# SMU_STPM_Board.net
KiCad netlist of a schematic drawn in Altium Designer
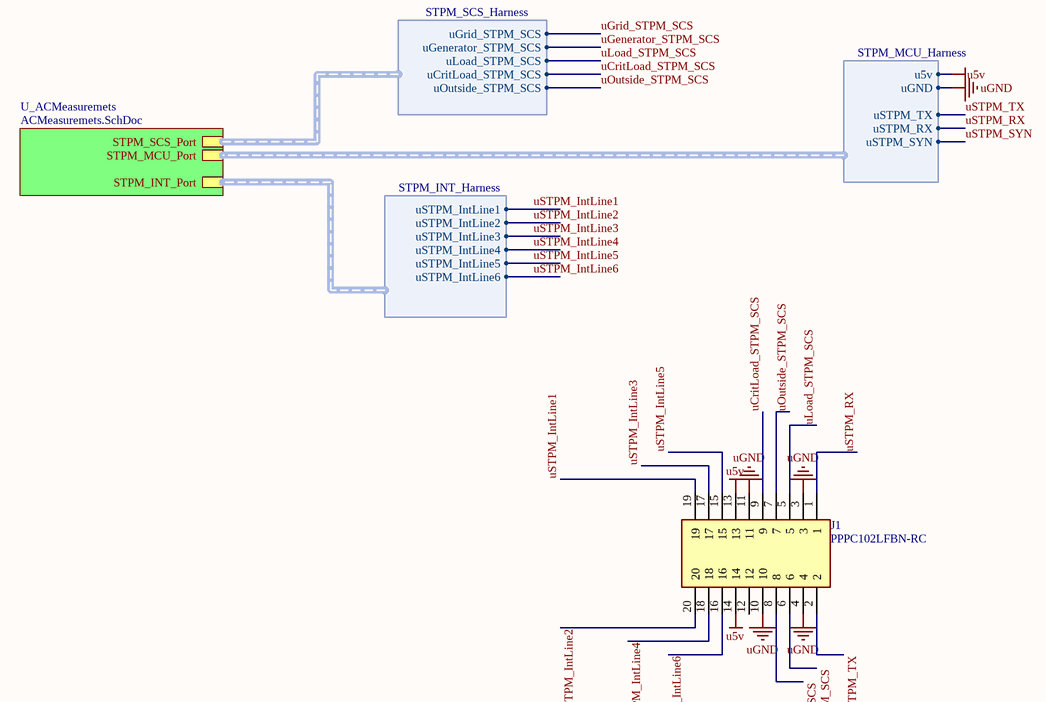
[diagram p0: SMU_STPM_Board.SchDoc]

(export (version "E")
  (design (tool "Eeschema 10.0.6"))
  (components
    (comp (ref "J1")
      (value "PPPC102LFBN-RC")
      (footprint "SamacSys:RHDR20W85P254_2X10_2590X508X880P")
      (description "Connector")
      (fields (field (name "DIGI-KEY_PART_NUMBER") "S6106-ND"))
      (libsource (lib "*") (part "PPPC102LFBN-RC"))
    )
  )
  (nets
    (net (code "4") (name "/uCritLoad_STPM_SCS") (class "Default")
      (node (ref "J1") (pin "9") (pinfunction "9_9") (pintype "passive"))
    )
    (net (code "5") (name "/uGenerator_STPM_SCS") (class "Default")
      (node (ref "J1") (pin "8") (pinfunction "8_8") (pintype "passive"))
    )
    (net (code "6") (name "/uGrid_STPM_SCS") (class "Default")
      (node (ref "J1") (pin "6") (pinfunction "6_6") (pintype "passive"))
    )
    (net (code "7") (name "/uLoad_STPM_SCS") (class "Default")
      (node (ref "J1") (pin "5") (pinfunction "5_5") (pintype "passive"))
    )
    (net (code "8") (name "/uOutside_STPM_SCS") (class "Default")
      (node (ref "J1") (pin "7") (pinfunction "7_7") (pintype "passive"))
    )
    (net (code "9") (name "/uSTPM_IntLine1") (class "Default")
      (node (ref "J1") (pin "19") (pinfunction "19_19") (pintype "passive"))
    )
    (net (code "10") (name "/uSTPM_IntLine2") (class "Default")
      (node (ref "J1") (pin "20") (pinfunction "20_20") (pintype "passive"))
    )
    (net (code "11") (name "/uSTPM_IntLine3") (class "Default")
      (node (ref "J1") (pin "17") (pinfunction "17_17") (pintype "passive"))
    )
    (net (code "12") (name "/uSTPM_IntLine4") (class "Default")
      (node (ref "J1") (pin "18") (pinfunction "18_18") (pintype "passive"))
    )
    (net (code "13") (name "/uSTPM_IntLine5") (class "Default")
      (node (ref "J1") (pin "15") (pinfunction "15_15") (pintype "passive"))
    )
    (net (code "14") (name "/uSTPM_IntLine6") (class "Default")
      (node (ref "J1") (pin "16") (pinfunction "16_16") (pintype "passive"))
    )
    (net (code "15") (name "/uSTPM_RX") (class "Default")
      (node (ref "J1") (pin "1") (pinfunction "1_1") (pintype "passive"))
    )
    (net (code "17") (name "/uSTPM_TX") (class "Default")
      (node (ref "J1") (pin "2") (pinfunction "2_2") (pintype "passive"))
    )
    (net (code "21") (name "u5v") (class "Default")
      (node (ref "J1") (pin "13") (pinfunction "13_13") (pintype "passive"))
      (node (ref "J1") (pin "14") (pinfunction "14_14") (pintype "passive"))
    )
    (net (code "22") (name "uGND") (class "Default")
      (node (ref "J1") (pin "10") (pinfunction "10_10") (pintype "passive"))
      (node (ref "J1") (pin "11") (pinfunction "11_11") (pintype "passive"))
      (node (ref "J1") (pin "3") (pinfunction "3_3") (pintype "passive"))
      (node (ref "J1") (pin "4") (pinfunction "4_4") (pintype "passive"))
    )
    (net (code "23") (name "unconnected-(J1-Pad12)") (class "Default")
      (node (ref "J1") (pin "12") (pinfunction "12_12") (pintype "passive"))
    )
  )
)
